# NAND_FLASH_TESTBENCH.net
KiCad netlist of a schematic drawn in EAGLE
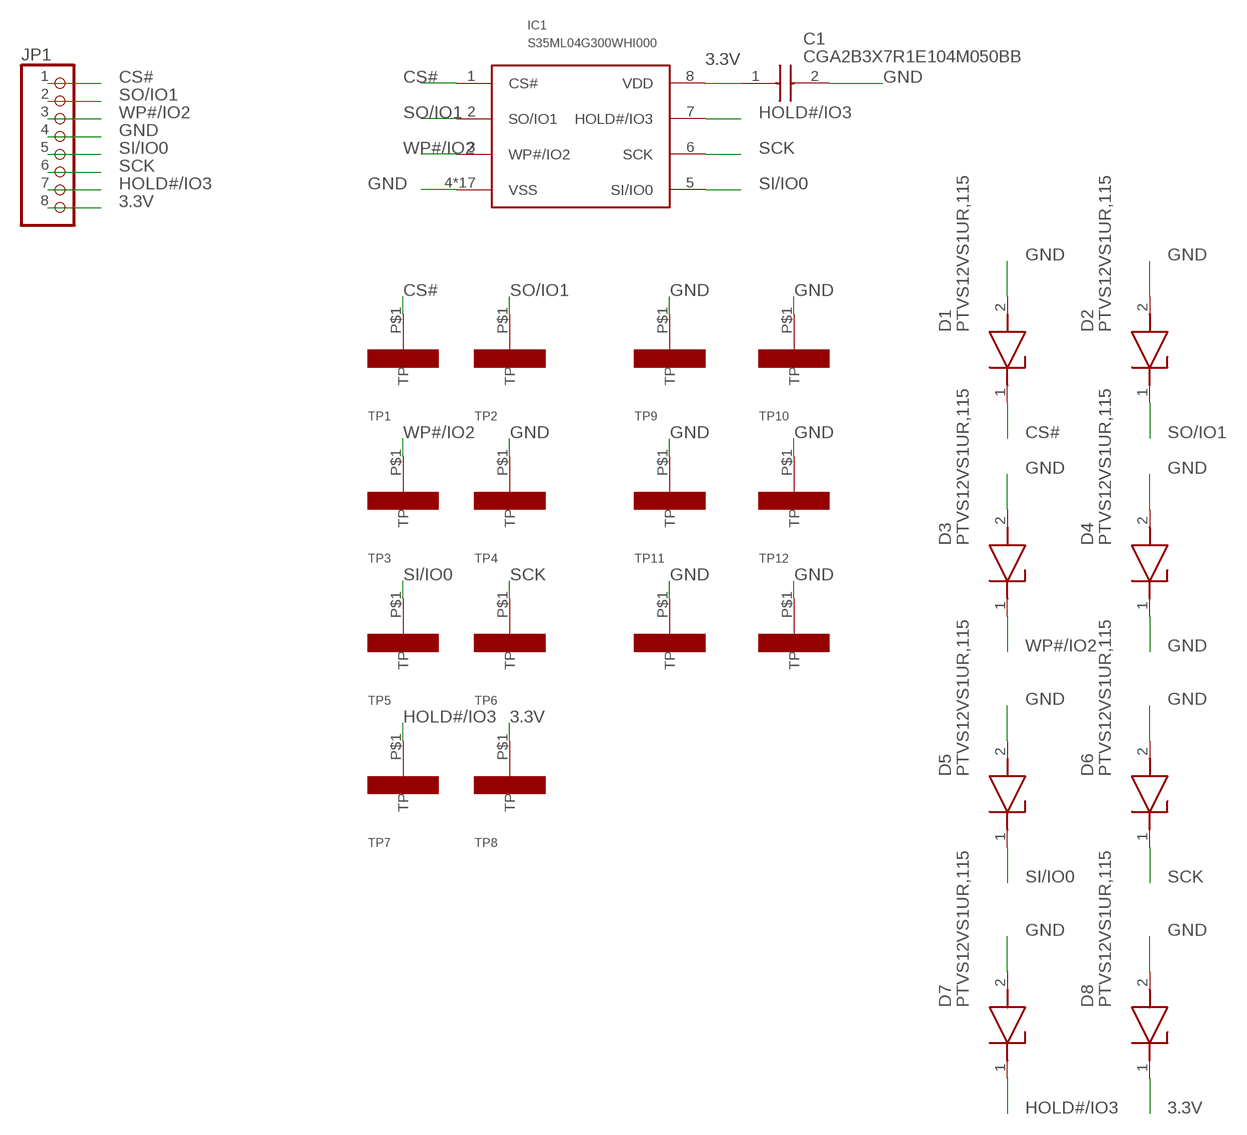
[diagram p0: schematic, sheet 1]

(export (version "E")
  (design (tool "Eeschema 10.0.6"))
  (components
    (comp (ref "C1")
      (value "CGA2B3X7R1E104M050BB")
      (footprint "eagle-import:CAPC1005X55N")
      (fields (field (name "MOUSER_PART_NUMBER") "810-CGA2B3X7R1E104MB"))
      (libsource (lib "eagle-import") (part "CGA2B3X7R1E104M050BB"))
    )
    (comp (ref "D1")
      (value "PTVS12VS1UR,115")
      (footprint "eagle-import:SOD123W")
      (fields (field (name "MOUSER_PART_NUMBER") "771-PTVS12VS1UR115"))
      (libsource (lib "eagle-import") (part "PTVS12VS1UR,115"))
    )
    (comp (ref "D2")
      (value "PTVS12VS1UR,115")
      (footprint "eagle-import:SOD123W")
      (fields (field (name "MOUSER_PART_NUMBER") "771-PTVS12VS1UR115"))
      (libsource (lib "eagle-import") (part "PTVS12VS1UR,115"))
    )
    (comp (ref "D3")
      (value "PTVS12VS1UR,115")
      (footprint "eagle-import:SOD123W")
      (fields (field (name "MOUSER_PART_NUMBER") "771-PTVS12VS1UR115"))
      (libsource (lib "eagle-import") (part "PTVS12VS1UR,115"))
    )
    (comp (ref "D4")
      (value "PTVS12VS1UR,115")
      (footprint "eagle-import:SOD123W")
      (fields (field (name "MOUSER_PART_NUMBER") "771-PTVS12VS1UR115"))
      (libsource (lib "eagle-import") (part "PTVS12VS1UR,115"))
    )
    (comp (ref "D5")
      (value "PTVS12VS1UR,115")
      (footprint "eagle-import:SOD123W")
      (fields (field (name "MOUSER_PART_NUMBER") "771-PTVS12VS1UR115"))
      (libsource (lib "eagle-import") (part "PTVS12VS1UR,115"))
    )
    (comp (ref "D6")
      (value "PTVS12VS1UR,115")
      (footprint "eagle-import:SOD123W")
      (fields (field (name "MOUSER_PART_NUMBER") "771-PTVS12VS1UR115"))
      (libsource (lib "eagle-import") (part "PTVS12VS1UR,115"))
    )
    (comp (ref "D7")
      (value "PTVS12VS1UR,115")
      (footprint "eagle-import:SOD123W")
      (fields (field (name "MOUSER_PART_NUMBER") "771-PTVS12VS1UR115"))
      (libsource (lib "eagle-import") (part "PTVS12VS1UR,115"))
    )
    (comp (ref "D8")
      (value "PTVS12VS1UR,115")
      (footprint "eagle-import:SOD123W")
      (fields (field (name "MOUSER_PART_NUMBER") "771-PTVS12VS1UR115"))
      (libsource (lib "eagle-import") (part "PTVS12VS1UR,115"))
    )
    (comp (ref "IC1")
      (value "S35ML04G300WHI000")
      (footprint "eagle-import:S35ML04G300WHI000")
      (libsource (lib "eagle-import") (part "S35ML04G300WHI000"))
    )
    (comp (ref "JP1")
      (value "PINHD-1X8")
      (footprint "eagle-import:1X08")
      (libsource (lib "eagle-import") (part "PINHD-1X8"))
    )
    (comp (ref "TP1")
      (value "S1751-46R")
      (footprint "eagle-import:1.85X3.45_MM")
      (libsource (lib "eagle-import") (part "S1751-46R"))
    )
    (comp (ref "TP2")
      (value "S1751-46R")
      (footprint "eagle-import:1.85X3.45_MM")
      (libsource (lib "eagle-import") (part "S1751-46R"))
    )
    (comp (ref "TP3")
      (value "S1751-46R")
      (footprint "eagle-import:1.85X3.45_MM")
      (libsource (lib "eagle-import") (part "S1751-46R"))
    )
    (comp (ref "TP4")
      (value "S1751-46R")
      (footprint "eagle-import:1.85X3.45_MM")
      (libsource (lib "eagle-import") (part "S1751-46R"))
    )
    (comp (ref "TP5")
      (value "S1751-46R")
      (footprint "eagle-import:1.85X3.45_MM")
      (libsource (lib "eagle-import") (part "S1751-46R"))
    )
    (comp (ref "TP6")
      (value "S1751-46R")
      (footprint "eagle-import:1.85X3.45_MM")
      (libsource (lib "eagle-import") (part "S1751-46R"))
    )
    (comp (ref "TP7")
      (value "S1751-46R")
      (footprint "eagle-import:1.85X3.45_MM")
      (libsource (lib "eagle-import") (part "S1751-46R"))
    )
    (comp (ref "TP8")
      (value "S1751-46R")
      (footprint "eagle-import:1.85X3.45_MM")
      (libsource (lib "eagle-import") (part "S1751-46R"))
    )
    (comp (ref "TP9")
      (value "S1751-46R")
      (footprint "eagle-import:1.85X3.45_MM")
      (libsource (lib "eagle-import") (part "S1751-46R"))
    )
    (comp (ref "TP10")
      (value "S1751-46R")
      (footprint "eagle-import:1.85X3.45_MM")
      (libsource (lib "eagle-import") (part "S1751-46R"))
    )
    (comp (ref "TP11")
      (value "S1751-46R")
      (footprint "eagle-import:1.85X3.45_MM")
      (libsource (lib "eagle-import") (part "S1751-46R"))
    )
    (comp (ref "TP12")
      (value "S1751-46R")
      (footprint "eagle-import:1.85X3.45_MM")
      (libsource (lib "eagle-import") (part "S1751-46R"))
    )
    (comp (ref "TP13")
      (value "S1751-46R")
      (footprint "eagle-import:1.85X3.45_MM")
      (libsource (lib "eagle-import") (part "S1751-46R"))
    )
    (comp (ref "TP14")
      (value "S1751-46R")
      (footprint "eagle-import:1.85X3.45_MM")
      (libsource (lib "eagle-import") (part "S1751-46R"))
    )
  )
  (nets
    (net (code "1") (name "/3.3V") (class "Default")
      (node (ref "C1") (pin "1") (pinfunction "1_1") (pintype "bidirectional"))
      (node (ref "D8") (pin "1") (pinfunction "K_1") (pintype "bidirectional"))
      (node (ref "IC1") (pin "8") (pinfunction "VDD_8") (pintype "bidirectional"))
      (node (ref "JP1") (pin "8") (pinfunction "8_8") (pintype "passive"))
      (node (ref "TP8") (pin "P$1") (pinfunction "TP_P$1") (pintype "bidirectional"))
    )
    (net (code "2") (name "/CS#") (class "Default")
      (node (ref "D1") (pin "1") (pinfunction "K_1") (pintype "bidirectional"))
      (node (ref "IC1") (pin "1") (pinfunction "CS#_1") (pintype "bidirectional"))
      (node (ref "JP1") (pin "1") (pinfunction "1_1") (pintype "passive"))
      (node (ref "TP1") (pin "P$1") (pinfunction "TP_P$1") (pintype "bidirectional"))
    )
    (net (code "3") (name "/GND") (class "Default")
      (node (ref "C1") (pin "2") (pinfunction "2_2") (pintype "bidirectional"))
      (node (ref "D1") (pin "2") (pinfunction "A_2") (pintype "bidirectional"))
      (node (ref "D2") (pin "2") (pinfunction "A_2") (pintype "bidirectional"))
      (node (ref "D3") (pin "2") (pinfunction "A_2") (pintype "bidirectional"))
      (node (ref "D4") (pin "1") (pinfunction "K_1") (pintype "bidirectional"))
      (node (ref "D4") (pin "2") (pinfunction "A_2") (pintype "bidirectional"))
      (node (ref "D5") (pin "2") (pinfunction "A_2") (pintype "bidirectional"))
      (node (ref "D6") (pin "2") (pinfunction "A_2") (pintype "bidirectional"))
      (node (ref "D7") (pin "2") (pinfunction "A_2") (pintype "bidirectional"))
      (node (ref "D8") (pin "2") (pinfunction "A_2") (pintype "bidirectional"))
      (node (ref "IC1") (pin "4") (pinfunction "VSS_4") (pintype "bidirectional"))
      (node (ref "IC1") (pin "P$1") (pinfunction "VSS_P$1") (pintype "bidirectional"))
      (node (ref "IC1") (pin "P$10") (pinfunction "VSS_P$10") (pintype "bidirectional"))
      (node (ref "IC1") (pin "P$11") (pinfunction "VSS_P$11") (pintype "bidirectional"))
      (node (ref "IC1") (pin "P$12") (pinfunction "VSS_P$12") (pintype "bidirectional"))
      (node (ref "IC1") (pin "P$13") (pinfunction "VSS_P$13") (pintype "bidirectional"))
      (node (ref "IC1") (pin "P$14") (pinfunction "VSS_P$14") (pintype "bidirectional"))
      (node (ref "IC1") (pin "P$15") (pinfunction "VSS_P$15") (pintype "bidirectional"))
      (node (ref "IC1") (pin "P$16") (pinfunction "VSS_P$16") (pintype "bidirectional"))
      (node (ref "IC1") (pin "P$2") (pinfunction "VSS_P$2") (pintype "bidirectional"))
      (node (ref "IC1") (pin "P$3") (pinfunction "VSS_P$3") (pintype "bidirectional"))
      (node (ref "IC1") (pin "P$4") (pinfunction "VSS_P$4") (pintype "bidirectional"))
      (node (ref "IC1") (pin "P$5") (pinfunction "VSS_P$5") (pintype "bidirectional"))
      (node (ref "IC1") (pin "P$6") (pinfunction "VSS_P$6") (pintype "bidirectional"))
      (node (ref "IC1") (pin "P$7") (pinfunction "VSS_P$7") (pintype "bidirectional"))
      (node (ref "IC1") (pin "P$8") (pinfunction "VSS_P$8") (pintype "bidirectional"))
      (node (ref "IC1") (pin "P$9") (pinfunction "VSS_P$9") (pintype "bidirectional"))
      (node (ref "JP1") (pin "4") (pinfunction "4_4") (pintype "passive"))
      (node (ref "TP10") (pin "P$1") (pinfunction "TP_P$1") (pintype "bidirectional"))
      (node (ref "TP11") (pin "P$1") (pinfunction "TP_P$1") (pintype "bidirectional"))
      (node (ref "TP12") (pin "P$1") (pinfunction "TP_P$1") (pintype "bidirectional"))
      (node (ref "TP13") (pin "P$1") (pinfunction "TP_P$1") (pintype "bidirectional"))
      (node (ref "TP14") (pin "P$1") (pinfunction "TP_P$1") (pintype "bidirectional"))
      (node (ref "TP4") (pin "P$1") (pinfunction "TP_P$1") (pintype "bidirectional"))
      (node (ref "TP9") (pin "P$1") (pinfunction "TP_P$1") (pintype "bidirectional"))
    )
    (net (code "4") (name "/HOLD#{slash}IO3") (class "Default")
      (node (ref "D7") (pin "1") (pinfunction "K_1") (pintype "bidirectional"))
      (node (ref "IC1") (pin "7") (pinfunction "HOLD#/IO3_7") (pintype "bidirectional"))
      (node (ref "JP1") (pin "7") (pinfunction "7_7") (pintype "passive"))
      (node (ref "TP7") (pin "P$1") (pinfunction "TP_P$1") (pintype "bidirectional"))
    )
    (net (code "5") (name "/SCK") (class "Default")
      (node (ref "D6") (pin "1") (pinfunction "K_1") (pintype "bidirectional"))
      (node (ref "IC1") (pin "6") (pinfunction "SCK_6") (pintype "bidirectional"))
      (node (ref "JP1") (pin "6") (pinfunction "6_6") (pintype "passive"))
      (node (ref "TP6") (pin "P$1") (pinfunction "TP_P$1") (pintype "bidirectional"))
    )
    (net (code "6") (name "/SI{slash}IO0") (class "Default")
      (node (ref "D5") (pin "1") (pinfunction "K_1") (pintype "bidirectional"))
      (node (ref "IC1") (pin "5") (pinfunction "SI/IO0_5") (pintype "bidirectional"))
      (node (ref "JP1") (pin "5") (pinfunction "5_5") (pintype "passive"))
      (node (ref "TP5") (pin "P$1") (pinfunction "TP_P$1") (pintype "bidirectional"))
    )
    (net (code "7") (name "/SO{slash}IO1") (class "Default")
      (node (ref "D2") (pin "1") (pinfunction "K_1") (pintype "bidirectional"))
      (node (ref "IC1") (pin "2") (pinfunction "SO/IO1_2") (pintype "bidirectional"))
      (node (ref "JP1") (pin "2") (pinfunction "2_2") (pintype "passive"))
      (node (ref "TP2") (pin "P$1") (pinfunction "TP_P$1") (pintype "bidirectional"))
    )
    (net (code "8") (name "/WP#{slash}IO2") (class "Default")
      (node (ref "D3") (pin "1") (pinfunction "K_1") (pintype "bidirectional"))
      (node (ref "IC1") (pin "3") (pinfunction "WP#/IO2_3") (pintype "bidirectional"))
      (node (ref "JP1") (pin "3") (pinfunction "3_3") (pintype "passive"))
      (node (ref "TP3") (pin "P$1") (pinfunction "TP_P$1") (pintype "bidirectional"))
    )
  )
)
